# MusicPlayer.net
KiCad netlist of a schematic drawn in EAGLE
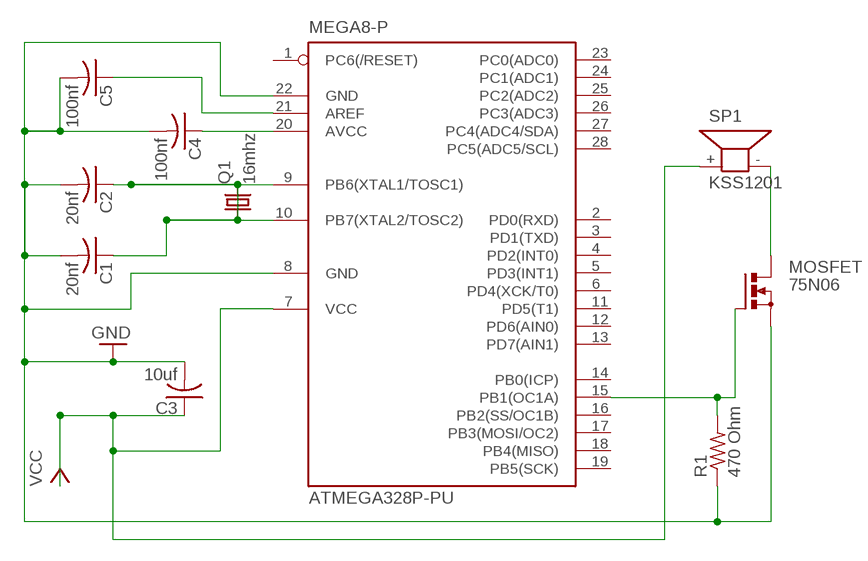
[diagram p0: schematic, sheet 1]

(export (version "E")
  (design (tool "Eeschema 10.0.6"))
  (components
    (comp (ref "ATMEGA328P-PU")
      (value "MEGA8-P")
      (footprint "eagle-import:DIL28-3")
      (libsource (lib "eagle-import") (part "MEGA8-P"))
    )
    (comp (ref "C1")
      (value "20nf")
      (footprint "eagle-import:C050-025X075")
      (libsource (lib "eagle-import") (part "C-US050-025X075"))
    )
    (comp (ref "C2")
      (value "20nf")
      (footprint "eagle-import:C050-025X075")
      (libsource (lib "eagle-import") (part "C-US050-025X075"))
    )
    (comp (ref "C3")
      (value "10uf")
      (footprint "eagle-import:C050-075X075")
      (libsource (lib "eagle-import") (part "C-US050-075X075"))
    )
    (comp (ref "C4")
      (value "100nf")
      (footprint "eagle-import:C050-025X075")
      (libsource (lib "eagle-import") (part "C-US050-025X075"))
    )
    (comp (ref "C5")
      (value "100nf")
      (footprint "eagle-import:C050-025X075")
      (libsource (lib "eagle-import") (part "C-US050-025X075"))
    )
    (comp (ref "MOSFET")
      (value "75N06")
      (footprint "eagle-import:TO220BH")
      (libsource (lib "eagle-import") (part "PMOSFET_NTO220BH"))
    )
    (comp (ref "Q1")
      (value "16mhz")
      (footprint "eagle-import:HC49U-V")
      (libsource (lib "eagle-import") (part "CRYSTALHC49U-V"))
    )
    (comp (ref "R1")
      (value "470 Ohm")
      (footprint "eagle-import:0204_5")
      (libsource (lib "eagle-import") (part "R-US_0204/5"))
    )
    (comp (ref "SP1")
      (value "KSS1201")
      (footprint "eagle-import:KSS1201")
      (libsource (lib "eagle-import") (part "KSS1201"))
    )
  )
  (nets
    (net (code "1") (name "GND") (class "Default")
      (node (ref "ATMEGA328P-PU") (pin "22") (pinfunction "GND_22") (pintype "power_in"))
      (node (ref "ATMEGA328P-PU") (pin "8") (pinfunction "GND_8") (pintype "power_in"))
      (node (ref "C1") (pin "2") (pinfunction "2_2") (pintype "passive"))
      (node (ref "C2") (pin "2") (pinfunction "2_2") (pintype "passive"))
      (node (ref "C3") (pin "2") (pinfunction "2_2") (pintype "passive"))
      (node (ref "C4") (pin "2") (pinfunction "2_2") (pintype "passive"))
      (node (ref "C5") (pin "2") (pinfunction "2_2") (pintype "passive"))
      (node (ref "MOSFET") (pin "S") (pinfunction "S_S") (pintype "passive"))
      (node (ref "R1") (pin "1") (pinfunction "1_1") (pintype "passive"))
    )
    (net (code "2") (name "Net-(ATMEGA328P-PU-AREF)") (class "Default")
      (node (ref "ATMEGA328P-PU") (pin "21") (pinfunction "AREF_21") (pintype "passive"))
      (node (ref "C5") (pin "1") (pinfunction "1_1") (pintype "passive"))
    )
    (net (code "3") (name "Net-(ATMEGA328P-PU-AVCC)") (class "Default")
      (node (ref "ATMEGA328P-PU") (pin "20") (pinfunction "AVCC_20") (pintype "power_in"))
      (node (ref "C4") (pin "1") (pinfunction "1_1") (pintype "passive"))
    )
    (net (code "4") (name "Net-(ATMEGA328P-PU-PB1(OC1A))") (class "Default")
      (node (ref "ATMEGA328P-PU") (pin "15") (pinfunction "PB1(OC1A)_15") (pintype "bidirectional"))
      (node (ref "MOSFET") (pin "G") (pinfunction "G_G") (pintype "passive"))
      (node (ref "R1") (pin "2") (pinfunction "2_2") (pintype "passive"))
    )
    (net (code "5") (name "Net-(ATMEGA328P-PU-PB6(XTAL1{slash}TOSC1))") (class "Default")
      (node (ref "ATMEGA328P-PU") (pin "10") (pinfunction "PB7(XTAL2/TOSC2)_10") (pintype "bidirectional"))
      (node (ref "ATMEGA328P-PU") (pin "9") (pinfunction "PB6(XTAL1/TOSC1)_9") (pintype "bidirectional"))
      (node (ref "C1") (pin "1") (pinfunction "1_1") (pintype "passive"))
      (node (ref "C2") (pin "1") (pinfunction "1_1") (pintype "passive"))
      (node (ref "Q1") (pin "1") (pinfunction "1_1") (pintype "passive"))
      (node (ref "Q1") (pin "2") (pinfunction "2_2") (pintype "passive"))
    )
    (net (code "6") (name "Net-(SP1-2)") (class "Default")
      (node (ref "MOSFET") (pin "D") (pinfunction "D_D") (pintype "passive"))
      (node (ref "SP1") (pin "-") (pinfunction "2_-") (pintype "passive"))
    )
    (net (code "7") (name "VCC") (class "Default")
      (node (ref "ATMEGA328P-PU") (pin "7") (pinfunction "VCC_7") (pintype "power_in"))
      (node (ref "C3") (pin "1") (pinfunction "1_1") (pintype "passive"))
      (node (ref "SP1") (pin "+") (pinfunction "1_+") (pintype "passive"))
    )
    (net (code "8") (name "unconnected-(ATMEGA328P-PU-PB0(ICP)-Pad14)") (class "Default")
      (node (ref "ATMEGA328P-PU") (pin "14") (pinfunction "PB0(ICP)_14") (pintype "bidirectional"))
    )
    (net (code "9") (name "unconnected-(ATMEGA328P-PU-PB2(SS{slash}OC1B)-Pad16)") (class "Default")
      (node (ref "ATMEGA328P-PU") (pin "16") (pinfunction "PB2(SS/OC1B)_16") (pintype "bidirectional"))
    )
    (net (code "10") (name "unconnected-(ATMEGA328P-PU-PB3(MOSI{slash}OC2)-Pad17)") (class "Default")
      (node (ref "ATMEGA328P-PU") (pin "17") (pinfunction "PB3(MOSI/OC2)_17") (pintype "bidirectional"))
    )
    (net (code "11") (name "unconnected-(ATMEGA328P-PU-PB4(MISO)-Pad18)") (class "Default")
      (node (ref "ATMEGA328P-PU") (pin "18") (pinfunction "PB4(MISO)_18") (pintype "bidirectional"))
    )
    (net (code "12") (name "unconnected-(ATMEGA328P-PU-PB5(SCK)-Pad19)") (class "Default")
      (node (ref "ATMEGA328P-PU") (pin "19") (pinfunction "PB5(SCK)_19") (pintype "bidirectional"))
    )
    (net (code "13") (name "unconnected-(ATMEGA328P-PU-PC0(ADC0)-Pad23)") (class "Default")
      (node (ref "ATMEGA328P-PU") (pin "23") (pinfunction "PC0(ADC0)_23") (pintype "bidirectional"))
    )
    (net (code "14") (name "unconnected-(ATMEGA328P-PU-PC1(ADC1)-Pad24)") (class "Default")
      (node (ref "ATMEGA328P-PU") (pin "24") (pinfunction "PC1(ADC1)_24") (pintype "bidirectional"))
    )
    (net (code "15") (name "unconnected-(ATMEGA328P-PU-PC2(ADC2)-Pad25)") (class "Default")
      (node (ref "ATMEGA328P-PU") (pin "25") (pinfunction "PC2(ADC2)_25") (pintype "bidirectional"))
    )
    (net (code "16") (name "unconnected-(ATMEGA328P-PU-PC3(ADC3)-Pad26)") (class "Default")
      (node (ref "ATMEGA328P-PU") (pin "26") (pinfunction "PC3(ADC3)_26") (pintype "bidirectional"))
    )
    (net (code "17") (name "unconnected-(ATMEGA328P-PU-PC4(ADC4{slash}SDA)-Pad27)") (class "Default")
      (node (ref "ATMEGA328P-PU") (pin "27") (pinfunction "PC4(ADC4/SDA)_27") (pintype "bidirectional"))
    )
    (net (code "18") (name "unconnected-(ATMEGA328P-PU-PC5(ADC5{slash}SCL)-Pad28)") (class "Default")
      (node (ref "ATMEGA328P-PU") (pin "28") (pinfunction "PC5(ADC5/SCL)_28") (pintype "bidirectional"))
    )
    (net (code "19") (name "unconnected-(ATMEGA328P-PU-PC6({slash}RESET)-Pad1)") (class "Default")
      (node (ref "ATMEGA328P-PU") (pin "1") (pinfunction "PC6(/RESET)_1") (pintype "bidirectional"))
    )
    (net (code "20") (name "unconnected-(ATMEGA328P-PU-PD0(RXD)-Pad2)") (class "Default")
      (node (ref "ATMEGA328P-PU") (pin "2") (pinfunction "PD0(RXD)_2") (pintype "bidirectional"))
    )
    (net (code "21") (name "unconnected-(ATMEGA328P-PU-PD1(TXD)-Pad3)") (class "Default")
      (node (ref "ATMEGA328P-PU") (pin "3") (pinfunction "PD1(TXD)_3") (pintype "bidirectional"))
    )
    (net (code "22") (name "unconnected-(ATMEGA328P-PU-PD2(INT0)-Pad4)") (class "Default")
      (node (ref "ATMEGA328P-PU") (pin "4") (pinfunction "PD2(INT0)_4") (pintype "bidirectional"))
    )
    (net (code "23") (name "unconnected-(ATMEGA328P-PU-PD3(INT1)-Pad5)") (class "Default")
      (node (ref "ATMEGA328P-PU") (pin "5") (pinfunction "PD3(INT1)_5") (pintype "bidirectional"))
    )
    (net (code "24") (name "unconnected-(ATMEGA328P-PU-PD4(XCK{slash}T0)-Pad6)") (class "Default")
      (node (ref "ATMEGA328P-PU") (pin "6") (pinfunction "PD4(XCK/T0)_6") (pintype "bidirectional"))
    )
    (net (code "25") (name "unconnected-(ATMEGA328P-PU-PD5(T1)-Pad11)") (class "Default")
      (node (ref "ATMEGA328P-PU") (pin "11") (pinfunction "PD5(T1)_11") (pintype "bidirectional"))
    )
    (net (code "26") (name "unconnected-(ATMEGA328P-PU-PD6(AIN0)-Pad12)") (class "Default")
      (node (ref "ATMEGA328P-PU") (pin "12") (pinfunction "PD6(AIN0)_12") (pintype "bidirectional"))
    )
    (net (code "27") (name "unconnected-(ATMEGA328P-PU-PD7(AIN1)-Pad13)") (class "Default")
      (node (ref "ATMEGA328P-PU") (pin "13") (pinfunction "PD7(AIN1)_13") (pintype "bidirectional"))
    )
  )
)
